# board.net
KiCad netlist of a schematic drawn in EAGLE
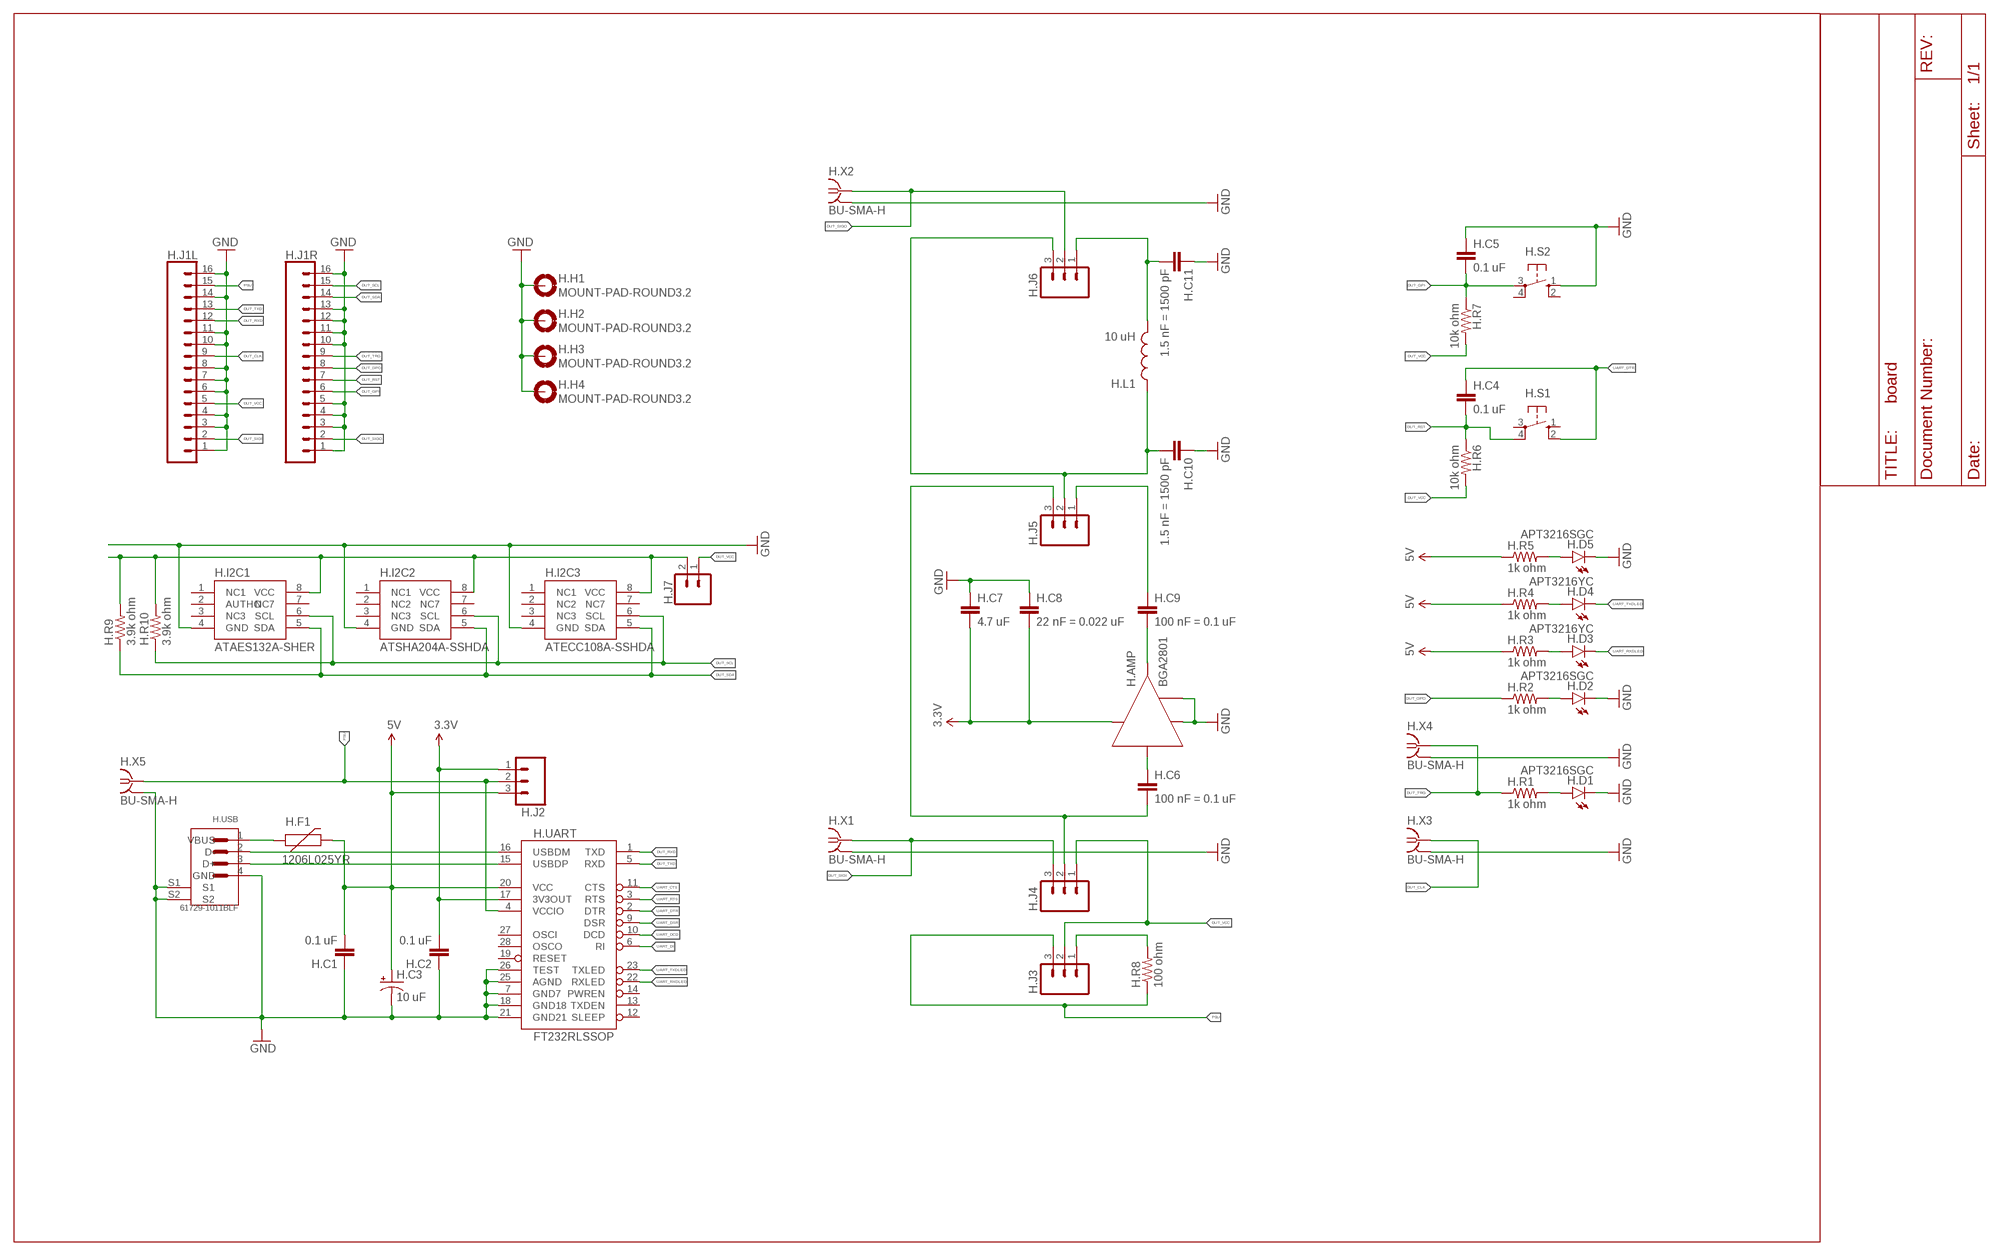
[diagram p0: schematic, sheet 1]

(export (version "E")
  (design (tool "Eeschema 10.0.6"))
  (components
    (comp (ref "H.AMP")
      (value "BGA2801")
      (footprint "eagle-import:SOT363")
      (libsource (lib "eagle-import") (part "BGA2801"))
    )
    (comp (ref "H.C1")
      (value "0.1 uF")
      (footprint "eagle-import:0603-CAP")
      (libsource (lib "eagle-import") (part "CAP0603-CAP"))
    )
    (comp (ref "H.C2")
      (value "0.1 uF")
      (footprint "eagle-import:0603-CAP")
      (libsource (lib "eagle-import") (part "CAP0603-CAP"))
    )
    (comp (ref "H.C3")
      (value "10 uF")
      (footprint "eagle-import:EIA3216")
      (libsource (lib "eagle-import") (part "CAP_POL1206"))
    )
    (comp (ref "H.C4")
      (value "0.1 uF")
      (footprint "eagle-import:0603-CAP")
      (libsource (lib "eagle-import") (part "CAP0603-CAP"))
    )
    (comp (ref "H.C5")
      (value "0.1 uF")
      (footprint "eagle-import:0603-CAP")
      (libsource (lib "eagle-import") (part "CAP0603-CAP"))
    )
    (comp (ref "H.C6")
      (value "100 nF = 0.1 uF")
      (footprint "eagle-import:0603-CAP")
      (libsource (lib "eagle-import") (part "CAP0603-CAP"))
    )
    (comp (ref "H.C7")
      (value "4.7 uF")
      (footprint "eagle-import:0603-CAP")
      (libsource (lib "eagle-import") (part "CAP0603-CAP"))
    )
    (comp (ref "H.C8")
      (value "22 nF = 0.022 uF")
      (footprint "eagle-import:0603-CAP")
      (libsource (lib "eagle-import") (part "CAP0603-CAP"))
    )
    (comp (ref "H.C9")
      (value "100 nF = 0.1 uF")
      (footprint "eagle-import:0603-CAP")
      (libsource (lib "eagle-import") (part "CAP0603-CAP"))
    )
    (comp (ref "H.C10")
      (value "1.5 nF = 1500 pF")
      (footprint "eagle-import:0603-CAP")
      (libsource (lib "eagle-import") (part "CAP0603-CAP"))
    )
    (comp (ref "H.C11")
      (value "1.5 nF = 1500 pF")
      (footprint "eagle-import:0603-CAP")
      (libsource (lib "eagle-import") (part "CAP0603-CAP"))
    )
    (comp (ref "H.D1")
      (value "APT3216SGC")
      (footprint "eagle-import:LED-1206")
      (libsource (lib "eagle-import") (part "LED-GREEN1206"))
    )
    (comp (ref "H.D2")
      (value "APT3216SGC")
      (footprint "eagle-import:LED-1206")
      (libsource (lib "eagle-import") (part "LED-GREEN1206"))
    )
    (comp (ref "H.D3")
      (value "APT3216YC")
      (footprint "eagle-import:LED-1206")
      (libsource (lib "eagle-import") (part "LED-YELLOW1206"))
    )
    (comp (ref "H.D4")
      (value "APT3216YC")
      (footprint "eagle-import:LED-1206")
      (libsource (lib "eagle-import") (part "LED-YELLOW1206"))
    )
    (comp (ref "H.D5")
      (value "APT3216SGC")
      (footprint "eagle-import:LED-1206")
      (libsource (lib "eagle-import") (part "LED-RED1206"))
    )
    (comp (ref "H.F1")
      (value "1206L025YR")
      (footprint "eagle-import:PTC-1206")
      (libsource (lib "eagle-import") (part "PTCSMD"))
    )
    (comp (ref "H.H1")
      (value "MOUNT-PAD-ROUND3.2")
      (footprint "eagle-import:3,2-PAD")
      (libsource (lib "eagle-import") (part "MOUNT-PAD-ROUND3.2"))
    )
    (comp (ref "H.H2")
      (value "MOUNT-PAD-ROUND3.2")
      (footprint "eagle-import:3,2-PAD")
      (libsource (lib "eagle-import") (part "MOUNT-PAD-ROUND3.2"))
    )
    (comp (ref "H.H3")
      (value "MOUNT-PAD-ROUND3.2")
      (footprint "eagle-import:3,2-PAD")
      (libsource (lib "eagle-import") (part "MOUNT-PAD-ROUND3.2"))
    )
    (comp (ref "H.H4")
      (value "MOUNT-PAD-ROUND3.2")
      (footprint "eagle-import:3,2-PAD")
      (libsource (lib "eagle-import") (part "MOUNT-PAD-ROUND3.2"))
    )
    (comp (ref "H.I2C1")
      (value "ATAES132A-SHER")
      (footprint "eagle-import:SO08")
      (libsource (lib "eagle-import") (part "ATAES132"))
    )
    (comp (ref "H.I2C2")
      (value "ATSHA204A-SSHDA")
      (footprint "eagle-import:SO08")
      (libsource (lib "eagle-import") (part "ATSHA204_SOIC8"))
    )
    (comp (ref "H.I2C3")
      (value "ATECC108A-SSHDA")
      (footprint "eagle-import:SO08")
      (libsource (lib "eagle-import") (part "ATECC108"))
    )
    (comp (ref "H.J1L")
      (value "CONN_16")
      (footprint "eagle-import:1X16")
      (libsource (lib "eagle-import") (part "CONN_16"))
    )
    (comp (ref "H.J1R")
      (value "CONN_16")
      (footprint "eagle-import:1X16")
      (libsource (lib "eagle-import") (part "CONN_16"))
    )
    (comp (ref "H.J2")
      (value "M03PTH")
      (footprint "eagle-import:1X03@1")
      (libsource (lib "eagle-import") (part "M03PTH"))
    )
    (comp (ref "H.J3")
      (value "M03PTH")
      (footprint "eagle-import:1X03@1")
      (libsource (lib "eagle-import") (part "M03PTH"))
    )
    (comp (ref "H.J4")
      (value "M03PTH")
      (footprint "eagle-import:1X03@1")
      (libsource (lib "eagle-import") (part "M03PTH"))
    )
    (comp (ref "H.J5")
      (value "M03PTH")
      (footprint "eagle-import:1X03@1")
      (libsource (lib "eagle-import") (part "M03PTH"))
    )
    (comp (ref "H.J6")
      (value "M03PTH")
      (footprint "eagle-import:1X03@1")
      (libsource (lib "eagle-import") (part "M03PTH"))
    )
    (comp (ref "H.J7")
      (value "CONN_02")
      (footprint "eagle-import:1X02")
      (libsource (lib "eagle-import") (part "CONN_02"))
    )
    (comp (ref "H.L1")
      (value "10 uH")
      (footprint "eagle-import:0603")
      (libsource (lib "eagle-import") (part "INDUCTOR0603"))
    )
    (comp (ref "H.R1")
      (value "1k ohm")
      (footprint "eagle-import:0603-RES")
      (libsource (lib "eagle-import") (part "RESISTOR0603-RES"))
    )
    (comp (ref "H.R2")
      (value "1k ohm")
      (footprint "eagle-import:0603-RES")
      (libsource (lib "eagle-import") (part "RESISTOR0603-RES"))
    )
    (comp (ref "H.R3")
      (value "1k ohm")
      (footprint "eagle-import:0603-RES")
      (libsource (lib "eagle-import") (part "RESISTOR0603-RES"))
    )
    (comp (ref "H.R4")
      (value "1k ohm")
      (footprint "eagle-import:0603-RES")
      (libsource (lib "eagle-import") (part "RESISTOR0603-RES"))
    )
    (comp (ref "H.R5")
      (value "1k ohm")
      (footprint "eagle-import:0603-RES")
      (libsource (lib "eagle-import") (part "RESISTOR0603-RES"))
    )
    (comp (ref "H.R6")
      (value "10k ohm")
      (footprint "eagle-import:0603-RES")
      (libsource (lib "eagle-import") (part "RESISTOR0603-RES"))
    )
    (comp (ref "H.R7")
      (value "10k ohm")
      (footprint "eagle-import:0603-RES")
      (libsource (lib "eagle-import") (part "RESISTOR0603-RES"))
    )
    (comp (ref "H.R8")
      (value "100 ohm")
      (footprint "eagle-import:0603-RES")
      (libsource (lib "eagle-import") (part "RESISTOR0603-RES"))
    )
    (comp (ref "H.R9")
      (value "3.9k ohm")
      (footprint "eagle-import:0603-RES")
      (libsource (lib "eagle-import") (part "RESISTOR0603-RES"))
    )
    (comp (ref "H.R10")
      (value "3.9k ohm")
      (footprint "eagle-import:0603-RES")
      (libsource (lib "eagle-import") (part "RESISTOR0603-RES"))
    )
    (comp (ref "H.S1")
      (value "40-XX")
      (footprint "eagle-import:B3F-40XX")
      (fields (field (name "MF") "OMRON COMPONENTS USA") (field (name "MPN") "B3F-4000"))
      (libsource (lib "eagle-import") (part "40-XX"))
    )
    (comp (ref "H.S2")
      (value "40-XX")
      (footprint "eagle-import:B3F-40XX")
      (fields (field (name "MF") "OMRON COMPONENTS USA") (field (name "MPN") "B3F-4000"))
      (libsource (lib "eagle-import") (part "40-XX"))
    )
    (comp (ref "H.UART")
      (value "FT232RLSSOP")
      (footprint "eagle-import:SSOP28DB")
      (libsource (lib "eagle-import") (part "FT232RLSSOP"))
    )
    (comp (ref "H.USB")
      (value "61729-1011BLF")
      (footprint "eagle-import:FCI_61729-1011BLF")
      (fields (field (name "MANUFACTURER") "Framatome"))
      (libsource (lib "eagle-import") (part "61729-1011BLF"))
    )
    (comp (ref "H.X1")
      (value "BU-SMA-H")
      (footprint "eagle-import:BU-SMA-H")
      (libsource (lib "eagle-import") (part "BU-SMA-H"))
    )
    (comp (ref "H.X2")
      (value "BU-SMA-H")
      (footprint "eagle-import:BU-SMA-H")
      (libsource (lib "eagle-import") (part "BU-SMA-H"))
    )
    (comp (ref "H.X3")
      (value "BU-SMA-H")
      (footprint "eagle-import:BU-SMA-H")
      (libsource (lib "eagle-import") (part "BU-SMA-H"))
    )
    (comp (ref "H.X4")
      (value "BU-SMA-H")
      (footprint "eagle-import:BU-SMA-H")
      (libsource (lib "eagle-import") (part "BU-SMA-H"))
    )
    (comp (ref "H.X5")
      (value "BU-SMA-H")
      (footprint "eagle-import:BU-SMA-H")
      (libsource (lib "eagle-import") (part "BU-SMA-H"))
    )
  )
  (nets
    (net (code "1") (name "3.3V") (class "Default")
      (node (ref "H.AMP") (pin "1") (pinfunction "VCC_1") (pintype "input"))
      (node (ref "H.C2") (pin "2") (pinfunction "2_2") (pintype "passive"))
      (node (ref "H.C7") (pin "2") (pinfunction "2_2") (pintype "passive"))
      (node (ref "H.C8") (pin "2") (pinfunction "2_2") (pintype "passive"))
      (node (ref "H.J2") (pin "1") (pinfunction "1_1") (pintype "passive"))
      (node (ref "H.UART") (pin "17") (pinfunction "3V3OUT_17") (pintype "output"))
    )
    (net (code "2") (name "5V") (class "Default")
      (node (ref "H.C1") (pin "2") (pinfunction "2_2") (pintype "passive"))
      (node (ref "H.C3") (pin "A") (pinfunction "+_A") (pintype "passive"))
      (node (ref "H.F1") (pin "2") (pinfunction "2_2") (pintype "bidirectional"))
      (node (ref "H.J2") (pin "3") (pinfunction "3_3") (pintype "passive"))
      (node (ref "H.R3") (pin "1") (pinfunction "1_1") (pintype "passive"))
      (node (ref "H.R4") (pin "1") (pinfunction "1_1") (pintype "passive"))
      (node (ref "H.R5") (pin "1") (pinfunction "1_1") (pintype "passive"))
      (node (ref "H.UART") (pin "20") (pinfunction "VCC_20") (pintype "power_in"))
    )
    (net (code "3") (name "DUT_CLK") (class "Default")
      (node (ref "H.J1L") (pin "9") (pinfunction "9_9") (pintype "passive"))
      (node (ref "H.X3") (pin "1") (pinfunction "1_1") (pintype "passive"))
    )
    (net (code "4") (name "DUT_GPI") (class "Default")
      (node (ref "H.C5") (pin "2") (pinfunction "2_2") (pintype "passive"))
      (node (ref "H.J1R") (pin "6") (pinfunction "6_6") (pintype "passive"))
      (node (ref "H.R7") (pin "1") (pinfunction "1_1") (pintype "passive"))
      (node (ref "H.S2") (pin "3") (pinfunction "P_3") (pintype "passive"))
    )
    (net (code "5") (name "DUT_GPO") (class "Default")
      (node (ref "H.J1R") (pin "8") (pinfunction "8_8") (pintype "passive"))
      (node (ref "H.R2") (pin "1") (pinfunction "1_1") (pintype "passive"))
    )
    (net (code "6") (name "DUT_RST") (class "Default")
      (node (ref "H.C4") (pin "2") (pinfunction "2_2") (pintype "passive"))
      (node (ref "H.J1R") (pin "7") (pinfunction "7_7") (pintype "passive"))
      (node (ref "H.R6") (pin "1") (pinfunction "1_1") (pintype "passive"))
      (node (ref "H.S1") (pin "4") (pinfunction "P1_4") (pintype "passive"))
    )
    (net (code "7") (name "DUT_RXD") (class "Default")
      (node (ref "H.J1L") (pin "12") (pinfunction "12_12") (pintype "passive"))
      (node (ref "H.UART") (pin "1") (pinfunction "TXD_1") (pintype "output"))
    )
    (net (code "8") (name "DUT_SCL") (class "Default")
      (node (ref "H.I2C1") (pin "6") (pinfunction "SCL_6") (pintype "bidirectional"))
      (node (ref "H.I2C2") (pin "6") (pinfunction "SCL_6") (pintype "bidirectional"))
      (node (ref "H.I2C3") (pin "6") (pinfunction "SCL_6") (pintype "bidirectional"))
      (node (ref "H.J1R") (pin "15") (pinfunction "15_15") (pintype "passive"))
      (node (ref "H.R10") (pin "1") (pinfunction "1_1") (pintype "passive"))
    )
    (net (code "9") (name "DUT_SDA") (class "Default")
      (node (ref "H.I2C1") (pin "5") (pinfunction "SDA_5") (pintype "bidirectional"))
      (node (ref "H.I2C2") (pin "5") (pinfunction "SDA_5") (pintype "bidirectional"))
      (node (ref "H.I2C3") (pin "5") (pinfunction "SDA_5") (pintype "bidirectional"))
      (node (ref "H.J1R") (pin "14") (pinfunction "14_14") (pintype "passive"))
      (node (ref "H.R9") (pin "1") (pinfunction "1_1") (pintype "passive"))
    )
    (net (code "10") (name "DUT_SIGI") (class "Default")
      (node (ref "H.J1L") (pin "2") (pinfunction "2_2") (pintype "passive"))
      (node (ref "H.J4") (pin "3") (pinfunction "3_3") (pintype "passive"))
      (node (ref "H.X1") (pin "1") (pinfunction "1_1") (pintype "passive"))
    )
    (net (code "11") (name "DUT_SIGO") (class "Default")
      (node (ref "H.J1R") (pin "2") (pinfunction "2_2") (pintype "passive"))
      (node (ref "H.J6") (pin "2") (pinfunction "2_2") (pintype "passive"))
      (node (ref "H.X2") (pin "1") (pinfunction "1_1") (pintype "passive"))
    )
    (net (code "12") (name "DUT_TRG") (class "Default")
      (node (ref "H.J1R") (pin "9") (pinfunction "9_9") (pintype "passive"))
      (node (ref "H.R1") (pin "1") (pinfunction "1_1") (pintype "passive"))
      (node (ref "H.X4") (pin "1") (pinfunction "1_1") (pintype "passive"))
    )
    (net (code "13") (name "DUT_TXD") (class "Default")
      (node (ref "H.J1L") (pin "13") (pinfunction "13_13") (pintype "passive"))
      (node (ref "H.UART") (pin "5") (pinfunction "RXD_5") (pintype "input"))
    )
    (net (code "14") (name "DUT_VCC") (class "Default")
      (node (ref "H.J1L") (pin "5") (pinfunction "5_5") (pintype "passive"))
      (node (ref "H.J3") (pin "2") (pinfunction "2_2") (pintype "passive"))
      (node (ref "H.J4") (pin "1") (pinfunction "1_1") (pintype "passive"))
      (node (ref "H.J7") (pin "1") (pinfunction "1_1") (pintype "passive"))
      (node (ref "H.R6") (pin "2") (pinfunction "2_2") (pintype "passive"))
      (node (ref "H.R7") (pin "2") (pinfunction "2_2") (pintype "passive"))
    )
    (net (code "15") (name "GND") (class "Default")
      (node (ref "H.AMP") (pin "2") (pinfunction "GND2_2") (pintype "input"))
      (node (ref "H.AMP") (pin "4") (pinfunction "GND1_4") (pintype "input"))
      (node (ref "H.AMP") (pin "5") (pinfunction "GND2_5") (pintype "input"))
      (node (ref "H.C1") (pin "1") (pinfunction "1_1") (pintype "passive"))
      (node (ref "H.C10") (pin "1") (pinfunction "1_1") (pintype "passive"))
      (node (ref "H.C11") (pin "1") (pinfunction "1_1") (pintype "passive"))
      (node (ref "H.C2") (pin "1") (pinfunction "1_1") (pintype "passive"))
      (node (ref "H.C3") (pin "C") (pinfunction "-_C") (pintype "passive"))
      (node (ref "H.C5") (pin "1") (pinfunction "1_1") (pintype "passive"))
      (node (ref "H.C7") (pin "1") (pinfunction "1_1") (pintype "passive"))
      (node (ref "H.C8") (pin "1") (pinfunction "1_1") (pintype "passive"))
      (node (ref "H.D1") (pin "C") (pinfunction "C_C") (pintype "passive"))
      (node (ref "H.D2") (pin "C") (pinfunction "C_C") (pintype "passive"))
      (node (ref "H.D5") (pin "C") (pinfunction "C_C") (pintype "passive"))
      (node (ref "H.H1") (pin "B3,2") (pinfunction "MOUNT_B3,2") (pintype "passive"))
      (node (ref "H.H2") (pin "B3,2") (pinfunction "MOUNT_B3,2") (pintype "passive"))
      (node (ref "H.H3") (pin "B3,2") (pinfunction "MOUNT_B3,2") (pintype "passive"))
      (node (ref "H.H4") (pin "B3,2") (pinfunction "MOUNT_B3,2") (pintype "passive"))
      (node (ref "H.I2C1") (pin "4") (pinfunction "GND_4") (pintype "power_in"))
      (node (ref "H.I2C2") (pin "4") (pinfunction "GND_4") (pintype "power_in"))
      (node (ref "H.I2C3") (pin "4") (pinfunction "GND_4") (pintype "power_in"))
      (node (ref "H.J1L") (pin "1") (pinfunction "1_1") (pintype "passive"))
      (node (ref "H.J1L") (pin "10") (pinfunction "10_10") (pintype "passive"))
      (node (ref "H.J1L") (pin "11") (pinfunction "11_11") (pintype "passive"))
      (node (ref "H.J1L") (pin "14") (pinfunction "14_14") (pintype "passive"))
      (node (ref "H.J1L") (pin "16") (pinfunction "16_16") (pintype "passive"))
      (node (ref "H.J1L") (pin "3") (pinfunction "3_3") (pintype "passive"))
      (node (ref "H.J1L") (pin "4") (pinfunction "4_4") (pintype "passive"))
      (node (ref "H.J1L") (pin "6") (pinfunction "6_6") (pintype "passive"))
      (node (ref "H.J1L") (pin "7") (pinfunction "7_7") (pintype "passive"))
      (node (ref "H.J1L") (pin "8") (pinfunction "8_8") (pintype "passive"))
      (node (ref "H.J1R") (pin "1") (pinfunction "1_1") (pintype "passive"))
      (node (ref "H.J1R") (pin "10") (pinfunction "10_10") (pintype "passive"))
      (node (ref "H.J1R") (pin "11") (pinfunction "11_11") (pintype "passive"))
      (node (ref "H.J1R") (pin "12") (pinfunction "12_12") (pintype "passive"))
      (node (ref "H.J1R") (pin "13") (pinfunction "13_13") (pintype "passive"))
      (node (ref "H.J1R") (pin "16") (pinfunction "16_16") (pintype "passive"))
      (node (ref "H.J1R") (pin "3") (pinfunction "3_3") (pintype "passive"))
      (node (ref "H.J1R") (pin "4") (pinfunction "4_4") (pintype "passive"))
      (node (ref "H.J1R") (pin "5") (pinfunction "5_5") (pintype "passive"))
      (node (ref "H.S2") (pin "1") (pinfunction "S_1") (pintype "passive"))
      (node (ref "H.UART") (pin "18") (pinfunction "GND18_18") (pintype "power_in"))
      (node (ref "H.UART") (pin "21") (pinfunction "GND21_21") (pintype "power_in"))
      (node (ref "H.UART") (pin "25") (pinfunction "AGND_25") (pintype "power_in"))
      (node (ref "H.UART") (pin "26") (pinfunction "TEST_26") (pintype "input"))
      (node (ref "H.UART") (pin "7") (pinfunction "GND7_7") (pintype "power_in"))
      (node (ref "H.USB") (pin "4") (pinfunction "GND_4") (pintype "power_in"))
      (node (ref "H.USB") (pin "S1") (pinfunction "S1_S1") (pintype "passive"))
      (node (ref "H.USB") (pin "S2") (pinfunction "S2_S2") (pintype "passive"))
      (node (ref "H.X1") (pin "2") (pinfunction "2_2") (pintype "passive"))
      (node (ref "H.X1") (pin "3") (pinfunction "2_3") (pintype "passive"))
      (node (ref "H.X1") (pin "4") (pinfunction "2_4") (pintype "passive"))
      (node (ref "H.X1") (pin "5") (pinfunction "2_5") (pintype "passive"))
      (node (ref "H.X2") (pin "2") (pinfunction "2_2") (pintype "passive"))
      (node (ref "H.X2") (pin "3") (pinfunction "2_3") (pintype "passive"))
      (node (ref "H.X2") (pin "4") (pinfunction "2_4") (pintype "passive"))
      (node (ref "H.X2") (pin "5") (pinfunction "2_5") (pintype "passive"))
      (node (ref "H.X3") (pin "2") (pinfunction "2_2") (pintype "passive"))
      (node (ref "H.X3") (pin "3") (pinfunction "2_3") (pintype "passive"))
      (node (ref "H.X3") (pin "4") (pinfunction "2_4") (pintype "passive"))
      (node (ref "H.X3") (pin "5") (pinfunction "2_5") (pintype "passive"))
      (node (ref "H.X4") (pin "2") (pinfunction "2_2") (pintype "passive"))
      (node (ref "H.X4") (pin "3") (pinfunction "2_3") (pintype "passive"))
      (node (ref "H.X4") (pin "4") (pinfunction "2_4") (pintype "passive"))
      (node (ref "H.X4") (pin "5") (pinfunction "2_5") (pintype "passive"))
      (node (ref "H.X5") (pin "2") (pinfunction "2_2") (pintype "passive"))
      (node (ref "H.X5") (pin "3") (pinfunction "2_3") (pintype "passive"))
      (node (ref "H.X5") (pin "4") (pinfunction "2_4") (pintype "passive"))
      (node (ref "H.X5") (pin "5") (pinfunction "2_5") (pintype "passive"))
    )
    (net (code "16") (name "Net-(H.AMP-RF_IN)") (class "Default")
      (node (ref "H.AMP") (pin "6") (pinfunction "RF_IN_6") (pintype "input"))
      (node (ref "H.C6") (pin "1") (pinfunction "1_1") (pintype "passive"))
    )
    (net (code "17") (name "Net-(H.AMP-RF_OUT)") (class "Default")
      (node (ref "H.AMP") (pin "3") (pinfunction "RF_OUT_3") (pintype "output"))
      (node (ref "H.C9") (pin "2") (pinfunction "2_2") (pintype "passive"))
    )
    (net (code "18") (name "Net-(H.C6-Pad2)") (class "Default")
      (node (ref "H.C6") (pin "2") (pinfunction "2_2") (pintype "passive"))
      (node (ref "H.J4") (pin "2") (pinfunction "2_2") (pintype "passive"))
      (node (ref "H.J5") (pin "3") (pinfunction "3_3") (pintype "passive"))
    )
    (net (code "19") (name "Net-(H.C9-Pad1)") (class "Default")
      (node (ref "H.C9") (pin "1") (pinfunction "1_1") (pintype "passive"))
      (node (ref "H.J5") (pin "1") (pinfunction "1_1") (pintype "passive"))
    )
    (net (code "20") (name "Net-(H.C10-Pad2)") (class "Default")
      (node (ref "H.C10") (pin "2") (pinfunction "2_2") (pintype "passive"))
      (node (ref "H.J5") (pin "2") (pinfunction "2_2") (pintype "passive"))
      (node (ref "H.J6") (pin "3") (pinfunction "3_3") (pintype "passive"))
      (node (ref "H.L1") (pin "1") (pinfunction "1_1") (pintype "passive"))
    )
    (net (code "21") (name "Net-(H.C11-Pad2)") (class "Default")
      (node (ref "H.C11") (pin "2") (pinfunction "2_2") (pintype "passive"))
      (node (ref "H.J6") (pin "1") (pinfunction "1_1") (pintype "passive"))
      (node (ref "H.L1") (pin "2") (pinfunction "2_2") (pintype "passive"))
    )
    (net (code "22") (name "Net-(H.D1-PadA)") (class "Default")
      (node (ref "H.D1") (pin "A") (pinfunction "A_A") (pintype "passive"))
      (node (ref "H.R1") (pin "2") (pinfunction "2_2") (pintype "passive"))
    )
    (net (code "23") (name "Net-(H.D2-PadA)") (class "Default")
      (node (ref "H.D2") (pin "A") (pinfunction "A_A") (pintype "passive"))
      (node (ref "H.R2") (pin "2") (pinfunction "2_2") (pintype "passive"))
    )
    (net (code "24") (name "Net-(H.D3-PadA)") (class "Default")
      (node (ref "H.D3") (pin "A") (pinfunction "A_A") (pintype "passive"))
      (node (ref "H.R3") (pin "2") (pinfunction "2_2") (pintype "passive"))
    )
    (net (code "25") (name "Net-(H.D4-PadA)") (class "Default")
      (node (ref "H.D4") (pin "A") (pinfunction "A_A") (pintype "passive"))
      (node (ref "H.R4") (pin "2") (pinfunction "2_2") (pintype "passive"))
    )
    (net (code "26") (name "Net-(H.D5-PadA)") (class "Default")
      (node (ref "H.D5") (pin "A") (pinfunction "A_A") (pintype "passive"))
      (node (ref "H.R5") (pin "2") (pinfunction "2_2") (pintype "passive"))
    )
    (net (code "27") (name "Net-(H.I2C1-VCC)") (class "Default")
      (node (ref "H.I2C1") (pin "8") (pinfunction "VCC_8") (pintype "power_in"))
      (node (ref "H.I2C2") (pin "8") (pinfunction "VCC_8") (pintype "power_in"))
      (node (ref "H.I2C3") (pin "8") (pinfunction "VCC_8") (pintype "power_in"))
      (node (ref "H.J7") (pin "2") (pinfunction "2_2") (pintype "passive"))
      (node (ref "H.R10") (pin "2") (pinfunction "2_2") (pintype "passive"))
      (node (ref "H.R9") (pin "2") (pinfunction "2_2") (pintype "passive"))
    )
    (net (code "28") (name "Net-(H.J3-Pad1)") (class "Default")
      (node (ref "H.J3") (pin "1") (pinfunction "1_1") (pintype "passive"))
      (node (ref "H.R8") (pin "2") (pinfunction "2_2") (pintype "passive"))
    )
    (net (code "29") (name "Net-(H.UART-USBDM)") (class "Default")
      (node (ref "H.UART") (pin "16") (pinfunction "USBDM_16") (pintype "bidirectional"))
      (node (ref "H.USB") (pin "2") (pinfunction "D-_2") (pintype "bidirectional"))
    )
    (net (code "30") (name "Net-(H.UART-USBDP)") (class "Default")
      (node (ref "H.UART") (pin "15") (pinfunction "USBDP_15") (pintype "bidirectional"))
      (node (ref "H.USB") (pin "3") (pinfunction "D+_3") (pintype "bidirectional"))
    )
    (net (code "31") (name "Net-(H.USB-VBUS)") (class "Default")
      (node (ref "H.F1") (pin "1") (pinfunction "1_1") (pintype "bidirectional"))
      (node (ref "H.USB") (pin "1") (pinfunction "VBUS_1") (pintype "power_in"))
    )
    (net (code "32") (name "PSU") (class "Default")
      (node (ref "H.J1L") (pin "15") (pinfunction "15_15") (pintype "passive"))
      (node (ref "H.J2") (pin "2") (pinfunction "2_2") (pintype "passive"))
      (node (ref "H.J3") (pin "3") (pinfunction "3_3") (pintype "passive"))
      (node (ref "H.R8") (pin "1") (pinfunction "1_1") (pintype "passive"))
      (node (ref "H.UART") (pin "4") (pinfunction "VCCIO_4") (pintype "power_in"))
      (node (ref "H.X5") (pin "1") (pinfunction "1_1") (pintype "passive"))
    )
    (net (code "33") (name "UART_CTS") (class "Default")
      (node (ref "H.UART") (pin "11") (pinfunction "CTS_11") (pintype "input"))
    )
    (net (code "34") (name "UART_DCD") (class "Default")
      (node (ref "H.UART") (pin "10") (pinfunction "DCD_10") (pintype "input"))
    )
    (net (code "35") (name "UART_DI") (class "Default")
      (node (ref "H.UART") (pin "6") (pinfunction "RI_6") (pintype "input"))
    )
    (net (code "36") (name "UART_DSR") (class "Default")
      (node (ref "H.UART") (pin "9") (pinfunction "DSR_9") (pintype "input"))
    )
    (net (code "37") (name "UART_DTR") (class "Default")
      (node (ref "H.C4") (pin "1") (pinfunction "1_1") (pintype "passive"))
      (node (ref "H.S1") (pin "2") (pinfunction "S1_2") (pintype "passive"))
      (node (ref "H.UART") (pin "2") (pinfunction "DTR_2") (pintype "output"))
    )
    (net (code "38") (name "UART_RTS") (class "Default")
      (node (ref "H.UART") (pin "3") (pinfunction "RTS_3") (pintype "output"))
    )
    (net (code "39") (name "UART_RXDLED") (class "Default")
      (node (ref "H.D3") (pin "C") (pinfunction "C_C") (pintype "passive"))
      (node (ref "H.UART") (pin "22") (pinfunction "RXLED_22") (pintype "input"))
    )
    (net (code "40") (name "UART_TXDLED") (class "Default")
      (node (ref "H.D4") (pin "C") (pinfunction "C_C") (pintype "passive"))
      (node (ref "H.UART") (pin "23") (pinfunction "TXLED_23") (pintype "input"))
    )
    (net (code "41") (name "unconnected-(H.I2C1-AUTHO-Pad2)") (class "Default")
      (node (ref "H.I2C1") (pin "2") (pinfunction "AUTHO_2") (pintype "bidirectional"))
    )
    (net (code "42") (name "unconnected-(H.I2C1-NC1-Pad1)") (class "Default")
      (node (ref "H.I2C1") (pin "1") (pinfunction "NC1_1") (pintype "no_connect"))
    )
    (net (code "43") (name "unconnected-(H.I2C1-NC3-Pad3)") (class "Default")
      (node (ref "H.I2C1") (pin "3") (pinfunction "NC3_3") (pintype "no_connect"))
    )
    (net (code "44") (name "unconnected-(H.I2C1-NC7-Pad7)") (class "Default")
      (node (ref "H.I2C1") (pin "7") (pinfunction "NC7_7") (pintype "no_connect"))
    )
    (net (code "45") (name "unconnected-(H.I2C2-NC1-Pad1)") (class "Default")
      (node (ref "H.I2C2") (pin "1") (pinfunction "NC1_1") (pintype "no_connect"))
    )
    (net (code "46") (name "unconnected-(H.I2C2-NC2-Pad2)") (class "Default")
      (node (ref "H.I2C2") (pin "2") (pinfunction "NC2_2") (pintype "no_connect"))
    )
    (net (code "47") (name "unconnected-(H.I2C2-NC3-Pad3)") (class "Default")
      (node (ref "H.I2C2") (pin "3") (pinfunction "NC3_3") (pintype "no_connect"))
    )
    (net (code "48") (name "unconnected-(H.I2C2-NC7-Pad7)") (class "Default")
      (node (ref "H.I2C2") (pin "7") (pinfunction "NC7_7") (pintype "no_connect"))
    )
    (net (code "49") (name "unconnected-(H.I2C3-NC1-Pad1)") (class "Default")
      (node (ref "H.I2C3") (pin "1") (pinfunction "NC1_1") (pintype "bidirectional"))
    )
    (net (code "50") (name "unconnected-(H.I2C3-NC2-Pad2)") (class "Default")
      (node (ref "H.I2C3") (pin "2") (pinfunction "NC2_2") (pintype "no_connect"))
    )
    (net (code "51") (name "unconnected-(H.I2C3-NC3-Pad3)") (class "Default")
      (node (ref "H.I2C3") (pin "3") (pinfunction "NC3_3") (pintype "no_connect"))
    )
    (net (code "52") (name "unconnected-(H.I2C3-NC7-Pad7)") (class "Default")
      (node (ref "H.I2C3") (pin "7") (pinfunction "NC7_7") (pintype "no_connect"))
    )
    (net (code "53") (name "unconnected-(H.S1-P-Pad3)") (class "Default")
      (node (ref "H.S1") (pin "3") (pinfunction "P_3") (pintype "passive"))
    )
    (net (code "54") (name "unconnected-(H.S1-S-Pad1)") (class "Default")
      (node (ref "H.S1") (pin "1") (pinfunction "S_1") (pintype "passive"))
    )
    (net (code "55") (name "unconnected-(H.S2-P1-Pad4)") (class "Default")
      (node (ref "H.S2") (pin "4") (pinfunction "P1_4") (pintype "passive"))
    )
    (net (code "56") (name "unconnected-(H.S2-S1-Pad2)") (class "Default")
      (node (ref "H.S2") (pin "2") (pinfunction "S1_2") (pintype "passive"))
    )
    (net (code "57") (name "unconnected-(H.UART-OSCI-Pad27)") (class "Default")
      (node (ref "H.UART") (pin "27") (pinfunction "OSCI_27") (pintype "input"))
    )
    (net (code "58") (name "unconnected-(H.UART-OSCO-Pad28)") (class "Default")
      (node (ref "H.UART") (pin "28") (pinfunction "OSCO_28") (pintype "output"))
    )
    (net (code "59") (name "unconnected-(H.UART-PWREN-Pad14)") (class "Default")
      (node (ref "H.UART") (pin "14") (pinfunction "PWREN_14") (pintype "input"))
    )
    (net (code "60") (name "unconnected-(H.UART-RESET-Pad19)") (class "Default")
      (node (ref "H.UART") (pin "19") (pinfunction "RESET_19") (pintype "input"))
    )
    (net (code "61") (name "unconnected-(H.UART-SLEEP-Pad12)") (class "Default")
      (node (ref "H.UART") (pin "12") (pinfunction "SLEEP_12") (pintype "input"))
    )
    (net (code "62") (name "unconnected-(H.UART-TXDEN-Pad13)") (class "Default")
      (node (ref "H.UART") (pin "13") (pinfunction "TXDEN_13") (pintype "input"))
    )
  )
)
